# CoproMKII_Coprocessor.net
KiCad netlist of a schematic drawn in Altium Designer
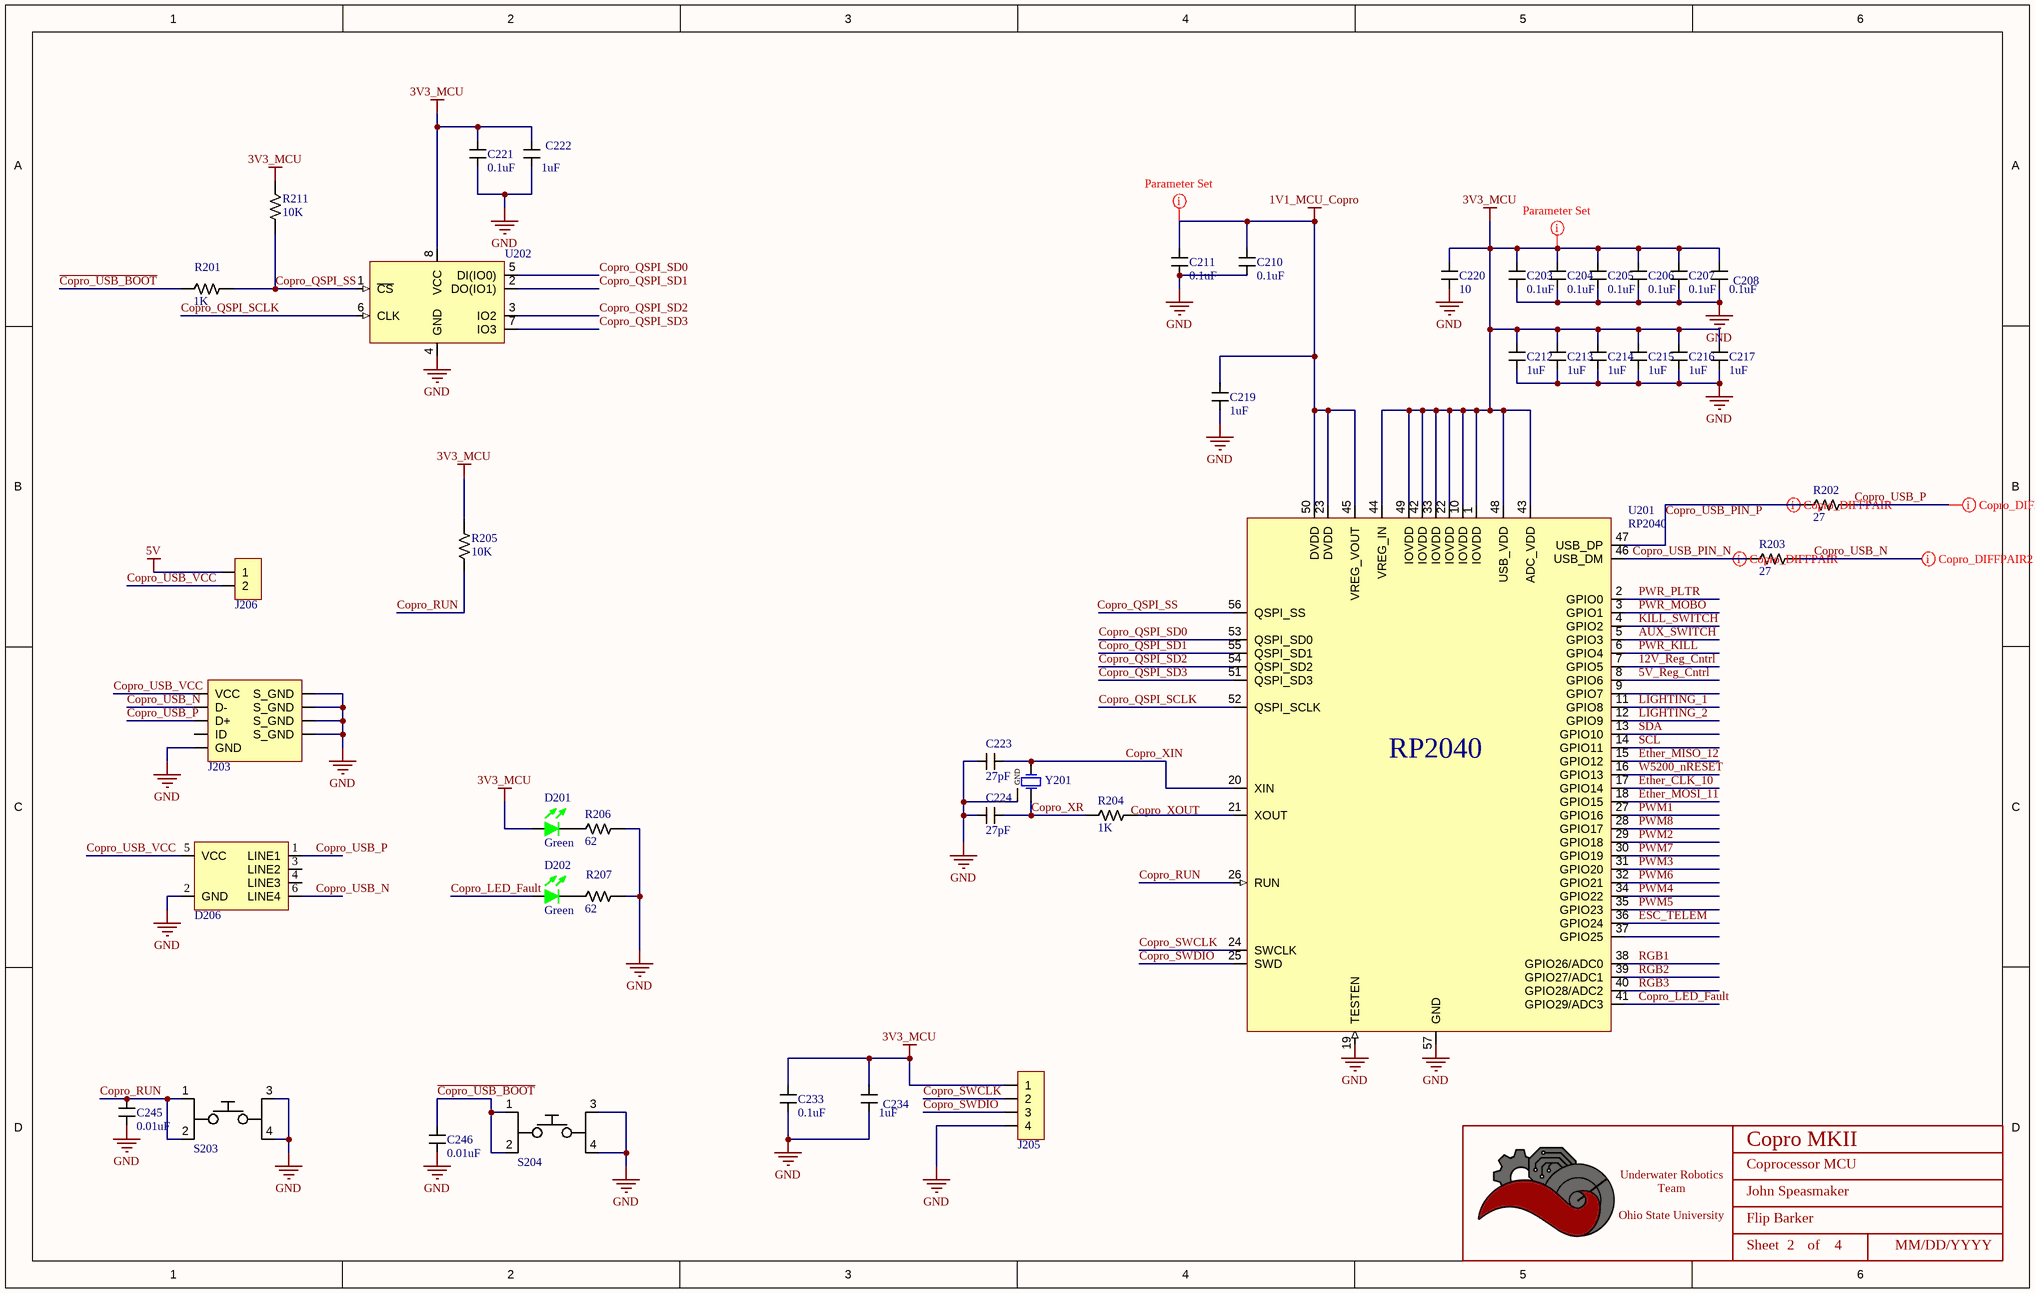
[diagram p0: CoproMKII_Coprocessor.SchDoc]

(export (version "E")
  (design (tool "Eeschema 10.0.6"))
  (components
    (comp (ref "C203")
      (value "0.1uF")
      (footprint "CAPACITOR_0603")
      (description "Cap 100nF 6.3V +/-10%\r\nCeramic 0603")
      (fields
        (field (name "TOLERANCE") "+/- 10%")
        (field (name "VOLTAGE") "6.3V")
        (field (name "MADE BY") "Flip B")
      )
      (libsource (lib "Capacitors") (part "CAPACITOR_0.1uF_0603"))
    )
    (comp (ref "C204")
      (value "0.1uF")
      (footprint "CAPACITOR_0603")
      (description "Cap 100nF 6.3V +/-10%\r\nCeramic 0603")
      (fields
        (field (name "TOLERANCE") "+/- 10%")
        (field (name "VOLTAGE") "6.3V")
        (field (name "MADE BY") "Flip B")
      )
      (libsource (lib "Capacitors") (part "CAPACITOR_0.1uF_0603"))
    )
    (comp (ref "C205")
      (value "0.1uF")
      (footprint "CAPACITOR_0603")
      (description "Cap 100nF 6.3V +/-10%\r\nCeramic 0603")
      (fields
        (field (name "TOLERANCE") "+/- 10%")
        (field (name "VOLTAGE") "6.3V")
        (field (name "MADE BY") "Flip B")
      )
      (libsource (lib "Capacitors") (part "CAPACITOR_0.1uF_0603"))
    )
    (comp (ref "C206")
      (value "0.1uF")
      (footprint "CAPACITOR_0603")
      (description "Cap 100nF 6.3V +/-10%\r\nCeramic 0603")
      (fields
        (field (name "TOLERANCE") "+/- 10%")
        (field (name "VOLTAGE") "6.3V")
        (field (name "MADE BY") "Flip B")
      )
      (libsource (lib "Capacitors") (part "CAPACITOR_0.1uF_0603"))
    )
    (comp (ref "C207")
      (value "0.1uF")
      (footprint "CAPACITOR_0603")
      (description "Cap 100nF 6.3V +/-10%\r\nCeramic 0603")
      (fields
        (field (name "TOLERANCE") "+/- 10%")
        (field (name "VOLTAGE") "6.3V")
        (field (name "MADE BY") "Flip B")
      )
      (libsource (lib "Capacitors") (part "CAPACITOR_0.1uF_0603"))
    )
    (comp (ref "C208")
      (value "0.1uF")
      (footprint "CAPACITOR_0603")
      (description "Cap 100nF 6.3V +/-10%\r\nCeramic 0603")
      (fields
        (field (name "TOLERANCE") "+/- 10%")
        (field (name "VOLTAGE") "6.3V")
        (field (name "MADE BY") "Flip B")
      )
      (libsource (lib "Capacitors") (part "CAPACITOR_0.1uF_0603"))
    )
    (comp (ref "C210")
      (value "0.1uF")
      (footprint "CAPACITOR_0603")
      (description "Cap 100nF 6.3V +/-10%\r\nCeramic 0603")
      (fields
        (field (name "TOLERANCE") "+/- 10%")
        (field (name "VOLTAGE") "6.3V")
        (field (name "MADE BY") "Flip B")
      )
      (libsource (lib "Capacitors") (part "CAPACITOR_0.1uF_0603"))
    )
    (comp (ref "C211")
      (value "0.1uF")
      (footprint "CAPACITOR_0603")
      (description "Cap 100nF 6.3V +/-10%\r\nCeramic 0603")
      (fields
        (field (name "TOLERANCE") "+/- 10%")
        (field (name "VOLTAGE") "6.3V")
        (field (name "MADE BY") "Flip B")
      )
      (libsource (lib "Capacitors") (part "CAPACITOR_0.1uF_0603"))
    )
    (comp (ref "C212")
      (value "1uF")
      (footprint "CAPACITOR_0603")
      (description "Cap 1uF 16V +/-10%\r\nCeramic 0603")
      (fields
        (field (name "TOLERANCE") "+/- 10%")
        (field (name "VOLTAGE") "16V")
        (field (name "MADE BY") "Flip B")
      )
      (libsource (lib "Capacitors") (part "CAPACITOR_1uF_0603"))
    )
    (comp (ref "C213")
      (value "1uF")
      (footprint "CAPACITOR_0603")
      (description "Cap 1uF 16V +/-10%\r\nCeramic 0603")
      (fields
        (field (name "TOLERANCE") "+/- 10%")
        (field (name "VOLTAGE") "16V")
        (field (name "MADE BY") "Flip B")
      )
      (libsource (lib "Capacitors") (part "CAPACITOR_1uF_0603"))
    )
    (comp (ref "C214")
      (value "1uF")
      (footprint "CAPACITOR_0603")
      (description "Cap 1uF 16V +/-10%\r\nCeramic 0603")
      (fields
        (field (name "TOLERANCE") "+/- 10%")
        (field (name "VOLTAGE") "16V")
        (field (name "MADE BY") "Flip B")
      )
      (libsource (lib "Capacitors") (part "CAPACITOR_1uF_0603"))
    )
    (comp (ref "C215")
      (value "1uF")
      (footprint "CAPACITOR_0603")
      (description "Cap 1uF 16V +/-10%\r\nCeramic 0603")
      (fields
        (field (name "TOLERANCE") "+/- 10%")
        (field (name "VOLTAGE") "16V")
        (field (name "MADE BY") "Flip B")
      )
      (libsource (lib "Capacitors") (part "CAPACITOR_1uF_0603"))
    )
    (comp (ref "C216")
      (value "1uF")
      (footprint "CAPACITOR_0603")
      (description "Cap 1uF 16V +/-10%\r\nCeramic 0603")
      (fields
        (field (name "TOLERANCE") "+/- 10%")
        (field (name "VOLTAGE") "16V")
        (field (name "MADE BY") "Flip B")
      )
      (libsource (lib "Capacitors") (part "CAPACITOR_1uF_0603"))
    )
    (comp (ref "C217")
      (value "1uF")
      (footprint "CAPACITOR_0603")
      (description "Cap 1uF 16V +/-10%\r\nCeramic 0603")
      (fields
        (field (name "TOLERANCE") "+/- 10%")
        (field (name "VOLTAGE") "16V")
        (field (name "MADE BY") "Flip B")
      )
      (libsource (lib "Capacitors") (part "CAPACITOR_1uF_0603"))
    )
    (comp (ref "C219")
      (value "1uF")
      (footprint "CAPACITOR_0603")
      (description "Cap 1uF 16V +/-10%\r\nCeramic 0603")
      (fields
        (field (name "TOLERANCE") "+/- 10%")
        (field (name "VOLTAGE") "16V")
        (field (name "MADE BY") "Flip B")
      )
      (libsource (lib "Capacitors") (part "CAPACITOR_1uF_0603"))
    )
    (comp (ref "C220")
      (value "10uF Ceramic 6.3V")
      (footprint "CAPACITOR_0603")
      (description "Cap 10uF 6.3V +/-20%\r\nCeramic 0603")
      (fields
        (field (name "TOLERANCE") "+/- 20%")
        (field (name "VOLTAGE") "6.3V")
        (field (name "VALUE (UF)") "10")
        (field (name "MADE BY") "Flip B")
      )
      (libsource (lib "Capacitors") (part "CAPACITOR_10uF_0603"))
    )
    (comp (ref "C221")
      (value "0.1uF")
      (footprint "CAPACITOR_0603")
      (description "Cap 100nF 6.3V +/-10%\r\nCeramic 0603")
      (fields
        (field (name "TOLERANCE") "+/- 10%")
        (field (name "VOLTAGE") "6.3V")
        (field (name "MADE BY") "Flip B")
      )
      (libsource (lib "Capacitors") (part "CAPACITOR_0.1uF_0603"))
    )
    (comp (ref "C222")
      (value "1uF")
      (footprint "CAPACITOR_0603")
      (description "Cap 1uF 16V +/-10%\r\nCeramic 0603")
      (fields
        (field (name "TOLERANCE") "+/- 10%")
        (field (name "VOLTAGE") "16V")
        (field (name "MADE BY") "Flip B")
      )
      (libsource (lib "Capacitors") (part "CAPACITOR_1uF_0603"))
    )
    (comp (ref "C223")
      (value "27pF")
      (footprint "CAPACITOR_0603")
      (description "Cap 27pF 50V +/-5%\r\nCeramic 0603")
      (fields
        (field (name "TOLERANCE") "+/- 5%")
        (field (name "VOLTAGE") "50V")
        (field (name "MADE BY") "Flip B")
      )
      (libsource (lib "Capacitors") (part "CAPACITOR_0.000027uF_0603"))
    )
    (comp (ref "C224")
      (value "27pF")
      (footprint "CAPACITOR_0603")
      (description "Cap 27pF 50V +/-5%\r\nCeramic 0603")
      (fields
        (field (name "TOLERANCE") "+/- 5%")
        (field (name "VOLTAGE") "50V")
        (field (name "MADE BY") "Flip B")
      )
      (libsource (lib "Capacitors") (part "CAPACITOR_0.000027uF_0603"))
    )
    (comp (ref "C233")
      (value "0.1uF")
      (footprint "CAPACITOR_0603")
      (description "Cap 100nF 6.3V +/-10%\r\nCeramic 0603")
      (fields
        (field (name "TOLERANCE") "+/- 10%")
        (field (name "VOLTAGE") "6.3V")
        (field (name "MADE BY") "Flip B")
      )
      (libsource (lib "Capacitors") (part "CAPACITOR_0.1uF_0603"))
    )
    (comp (ref "C234")
      (value "1uF")
      (footprint "CAPACITOR_0603")
      (description "Cap 1uF 16V +/-10%\r\nCeramic 0603")
      (fields
        (field (name "TOLERANCE") "+/- 10%")
        (field (name "VOLTAGE") "16V")
        (field (name "MADE BY") "Flip B")
      )
      (libsource (lib "Capacitors") (part "CAPACITOR_1uF_0603"))
    )
    (comp (ref "C245")
      (value "0.01uF")
      (footprint "CAPACITOR_0603")
      (description "Cap 10nF 6.3V +/-20%\r\nCeramic 0603")
      (fields
        (field (name "TOLERANCE") "+/- 10%")
        (field (name "VOLTAGE") "6.3V")
        (field (name "MADE BY") "Flip B")
      )
      (libsource (lib "Capacitors") (part "CAPACITOR_0.01uF_0603"))
    )
    (comp (ref "C246")
      (value "0.01uF")
      (footprint "CAPACITOR_0603")
      (description "Cap 10nF 6.3V +/-20%\r\nCeramic 0603")
      (fields
        (field (name "TOLERANCE") "+/- 10%")
        (field (name "VOLTAGE") "6.3V")
        (field (name "MADE BY") "Flip B")
      )
      (libsource (lib "Capacitors") (part "CAPACITOR_0.01uF_0603"))
    )
    (comp (ref "D201")
      (value "IN-S63AT5G")
      (footprint "LED_0603")
      (description "LED Green Vf= 3V If = 0.005A\r\nIN-S63AT5G")
      (fields (field (name "COLOR") "Green") (field (name "MADE BY") "Robert Pafford"))
      (libsource (lib "Diodes") (part "LED_Green_0603_3V"))
    )
    (comp (ref "D202")
      (value "IN-S63AT5G")
      (footprint "LED_0603")
      (description "LED Green Vf= 3V If = 0.005A\r\nIN-S63AT5G")
      (fields (field (name "COLOR") "Green") (field (name "MADE BY") "Robert Pafford"))
      (libsource (lib "Diodes") (part "LED_Green_0603_3V"))
    )
    (comp (ref "D206")
      (value "TVS DIODE 5VWM 25VC SOT23-6")
      (footprint "SOT 23-6L")
      (description "25V Clamp 6A (8/20µs) Ipp Tvs Diode Surface Mount SOT-23-6")
      (fields (field (name "MADE BY") "Robert Pafford"))
      (libsource (lib "Diodes") (part "RCLAMP0504S.TCT"))
    )
    (comp (ref "J203")
      (value "USB_MICRO R/A")
      (footprint "CONN_MINIUSB")
      (description "Amphenol Micro USB-B\r\nUSB2.0 5 Pin Right Angle SMD")
      (fields (field (name "MANUFACTURER") "Amphenol") (field (name "CREATED BY") "Flip B"))
      (libsource (lib "Connectors") (part "CONN_MICROUSB"))
    )
    (comp (ref "J205")
      (value "CONN HEADER VERT 4POS 2.54MM")
      (footprint "HEADER_4PIN_2.54MM")
      (fields (field (name "MADE BY") "Robert Pafford"))
      (libsource (lib "Connectors") (part "HEADER_4PIN_2.54MM"))
    )
    (comp (ref "J206")
      (value "2 POS")
      (footprint "HEADER_2PIN_2.54MM")
      (description "CONN HEADER VERT 2POS 2.54MM")
      (fields (field (name "CREATED BY") "Robert P"))
      (libsource (lib "Connectors") (part "HEADER_2PIN_2.54MM"))
    )
    (comp (ref "R201")
      (value "1k Ohm 5% 1/8W")
      (footprint "RESISTOR_0603")
      (description "RES 1k OHM 5% 1/8W 0603")
      (fields
        (field (name "TOLERANCE") "+/- 5%")
        (field (name "VALUE  (OHMS)") "1K")
        (field (name "MADE BY") "Robert Pafford")
      )
      (libsource (lib "Resistors") (part "RESISTOR_1K_0603"))
    )
    (comp (ref "R202")
      (value "27 Ohm 5% 1/8W")
      (footprint "RESISTOR_0603")
      (description "RES 27 OHM 5% 1/8W 0603")
      (fields
        (field (name "TOLERANCE") "+/- 5%")
        (field (name "VALUE  (OHMS)") "27")
        (field (name "MADE BY") "Robert Pafford")
      )
      (libsource (lib "Resistors") (part "RESISTOR_27_0603"))
    )
    (comp (ref "R203")
      (value "27 Ohm 5% 1/8W")
      (footprint "RESISTOR_0603")
      (description "RES 27 OHM 5% 1/8W 0603")
      (fields
        (field (name "TOLERANCE") "+/- 5%")
        (field (name "VALUE  (OHMS)") "27")
        (field (name "MADE BY") "Robert Pafford")
      )
      (libsource (lib "Resistors") (part "RESISTOR_27_0603"))
    )
    (comp (ref "R204")
      (value "1k Ohm 5% 1/8W")
      (footprint "RESISTOR_0603")
      (description "RES 1k OHM 5% 1/8W 0603")
      (fields
        (field (name "TOLERANCE") "+/- 5%")
        (field (name "VALUE  (OHMS)") "1K")
        (field (name "MADE BY") "Robert Pafford")
      )
      (libsource (lib "Resistors") (part "RESISTOR_1K_0603"))
    )
    (comp (ref "R205")
      (value "10k Ohm 5% 1/10W")
      (footprint "RESISTOR_0603")
      (description "RES 10k OHM 5% 1/10W 0603")
      (fields
        (field (name "TOLERANCE") "+/- 5%")
        (field (name "VALUE  (OHMS)") "10K")
        (field (name "MADE BY") "Robert Pafford")
      )
      (libsource (lib "Resistors") (part "RESISTOR_10K_0603"))
    )
    (comp (ref "R206")
      (value "62 Ohm 1% 1/4W")
      (footprint "RESISTOR_0603")
      (description "RES SMD 62 OHM 1% 1/4W 0603")
      (fields
        (field (name "TOLERANCE") "+/- 1%")
        (field (name "VALUE  (OHMS)") "62")
        (field (name "MADE BY") "Robert Pafford")
      )
      (libsource (lib "Resistors") (part "RESISTOR_62_0603"))
    )
    (comp (ref "R207")
      (value "62 Ohm 1% 1/4W")
      (footprint "RESISTOR_0603")
      (description "RES SMD 62 OHM 1% 1/4W 0603")
      (fields
        (field (name "TOLERANCE") "+/- 1%")
        (field (name "VALUE  (OHMS)") "62")
        (field (name "MADE BY") "Robert Pafford")
      )
      (libsource (lib "Resistors") (part "RESISTOR_62_0603"))
    )
    (comp (ref "R211")
      (value "10k Ohm 5% 1/10W")
      (footprint "RESISTOR_0603")
      (description "RES 10k OHM 5% 1/10W 0603")
      (fields
        (field (name "TOLERANCE") "+/- 5%")
        (field (name "VALUE  (OHMS)") "10K")
        (field (name "MADE BY") "Robert Pafford")
      )
      (libsource (lib "Resistors") (part "RESISTOR_10K_0603"))
    )
    (comp (ref "S203")
      (value "SPST Tactile Switch")
      (footprint "TactileSwitch")
      (description "SWITCH TACTILE SPST-NO 0.05A 12V")
      (fields (field (name "MADE BY") "Robert Pafford"))
      (libsource (lib "Switches") (part "Tactile Switch"))
    )
    (comp (ref "S204")
      (value "SPST Tactile Switch")
      (footprint "TactileSwitch")
      (description "SWITCH TACTILE SPST-NO 0.05A 12V")
      (fields (field (name "MADE BY") "Robert Pafford"))
      (libsource (lib "Switches") (part "Tactile Switch"))
    )
    (comp (ref "U201")
      (value "RP2040")
      (footprint "QFN-56 RP2040")
      (description "Raspberry Pi RP2040")
      (fields (field (name "MADE BY") "Robert Pafford"))
      (libsource (lib "Integrated Circuits") (part "RP2040"))
    )
    (comp (ref "U202")
      (value "W25Q128JVSIQ")
      (footprint "SOIC-8 W25QxJV")
      (description "IC FLASH 128MBIT SPI/QUAD 8SOIC")
      (fields (field (name "MADE BY") "Robert Pafford"))
      (libsource (lib "Integrated Circuits") (part "W25Q128JVSIQ"))
    )
    (comp (ref "Y201")
      (value "CRYSTAL 12.0000MHZ 18PF SMD")
      (footprint "4-SMD No Lead Crystal")
      (description "12 MHz ±20ppm Crystal 18pF 50 Ohms 4-SMD, No Lead")
      (fields (field (name "MADE BY") "Siddharth Venkatesan"))
      (libsource (lib "Crystals") (part "CRYSTAL_12MHz_SMD"))
    )
  )
  (nets
    (net (code "1") (name "/5V_Reg_Cntrl") (class "Default")
      (node (ref "U201") (pin "8") (pinfunction "GPIO6_8") (pintype "bidirectional"))
    )
    (net (code "2") (name "/12V_Reg_Cntrl") (class "Default")
      (node (ref "U201") (pin "7") (pinfunction "GPIO5_7") (pintype "bidirectional"))
    )
    (net (code "3") (name "/AUX_SWITCH") (class "Default")
      (node (ref "U201") (pin "5") (pinfunction "GPIO3_5") (pintype "bidirectional"))
    )
    (net (code "4") (name "/Copro_LED_Fault") (class "Default")
      (node (ref "D202") (pin "1") (pinfunction "1_1") (pintype "passive"))
      (node (ref "U201") (pin "41") (pinfunction "GPIO29/ADC3_41") (pintype "bidirectional"))
    )
    (net (code "5") (name "/Copro_QSPI_SCLK") (class "Default")
      (node (ref "U201") (pin "52") (pinfunction "QSPI_SCLK_52") (pintype "bidirectional"))
      (node (ref "U202") (pin "6") (pinfunction "CLK_6") (pintype "input"))
    )
    (net (code "6") (name "/Copro_QSPI_SD0") (class "Default")
      (node (ref "U201") (pin "53") (pinfunction "QSPI_SD0_53") (pintype "bidirectional"))
      (node (ref "U202") (pin "5") (pinfunction "DI(IO0)_5") (pintype "bidirectional"))
    )
    (net (code "7") (name "/Copro_QSPI_SD1") (class "Default")
      (node (ref "U201") (pin "55") (pinfunction "QSPI_SD1_55") (pintype "bidirectional"))
      (node (ref "U202") (pin "2") (pinfunction "DO(IO1)_2") (pintype "bidirectional"))
    )
    (net (code "8") (name "/Copro_QSPI_SD2") (class "Default")
      (node (ref "U201") (pin "54") (pinfunction "QSPI_SD2_54") (pintype "bidirectional"))
      (node (ref "U202") (pin "3") (pinfunction "IO2_3") (pintype "bidirectional"))
    )
    (net (code "9") (name "/Copro_QSPI_SD3") (class "Default")
      (node (ref "U201") (pin "51") (pinfunction "QSPI_SD3_51") (pintype "bidirectional"))
      (node (ref "U202") (pin "7") (pinfunction "IO3_7") (pintype "bidirectional"))
    )
    (net (code "10") (name "/Copro_QSPI_SS") (class "Default")
      (node (ref "R201") (pin "1") (pinfunction "1_1") (pintype "passive"))
      (node (ref "R211") (pin "1") (pinfunction "1_1") (pintype "passive"))
      (node (ref "U201") (pin "56") (pinfunction "QSPI_SS_56") (pintype "bidirectional"))
      (node (ref "U202") (pin "1") (pinfunction "~{CS}_1") (pintype "input"))
    )
    (net (code "11") (name "/Copro_RUN") (class "Default")
      (node (ref "C245") (pin "1") (pinfunction "1_1") (pintype "passive"))
      (node (ref "R205") (pin "2") (pinfunction "2_2") (pintype "passive"))
      (node (ref "S203") (pin "1") (pinfunction "1_1") (pintype "passive"))
      (node (ref "S203") (pin "2") (pinfunction "2_2") (pintype "passive"))
      (node (ref "U201") (pin "26") (pinfunction "RUN_26") (pintype "input"))
    )
    (net (code "12") (name "/Copro_SWCLK") (class "Default")
      (node (ref "J205") (pin "2") (pinfunction "2_2") (pintype "passive"))
      (node (ref "U201") (pin "24") (pinfunction "SWCLK_24") (pintype "bidirectional"))
    )
    (net (code "13") (name "/Copro_SWDIO") (class "Default")
      (node (ref "J205") (pin "3") (pinfunction "3_3") (pintype "passive"))
      (node (ref "U201") (pin "25") (pinfunction "SWD_25") (pintype "bidirectional"))
    )
    (net (code "14") (name "/Copro_USB_N") (class "Default")
      (node (ref "D206") (pin "6") (pinfunction "LINE4_6") (pintype "passive"))
      (node (ref "J203") (pin "2") (pinfunction "D-_2") (pintype "passive"))
      (node (ref "R203") (pin "1") (pinfunction "1_1") (pintype "passive"))
    )
    (net (code "15") (name "/Copro_USB_P") (class "Default")
      (node (ref "D206") (pin "1") (pinfunction "LINE1_1") (pintype "passive"))
      (node (ref "J203") (pin "3") (pinfunction "D+_3") (pintype "passive"))
      (node (ref "R202") (pin "1") (pinfunction "1_1") (pintype "passive"))
    )
    (net (code "16") (name "/Copro_USB_PIN_N") (class "Default")
      (node (ref "R203") (pin "2") (pinfunction "2_2") (pintype "passive"))
      (node (ref "U201") (pin "46") (pinfunction "USB_DM_46") (pintype "bidirectional"))
    )
    (net (code "17") (name "/Copro_USB_PIN_P") (class "Default")
      (node (ref "R202") (pin "2") (pinfunction "2_2") (pintype "passive"))
      (node (ref "U201") (pin "47") (pinfunction "USB_DP_47") (pintype "bidirectional"))
    )
    (net (code "18") (name "/Copro_USB_VCC") (class "Default")
      (node (ref "D206") (pin "5") (pinfunction "VCC_5") (pintype "power_in"))
      (node (ref "J203") (pin "1") (pinfunction "VCC_1") (pintype "passive"))
      (node (ref "J206") (pin "2") (pinfunction "2_2") (pintype "passive"))
    )
    (net (code "19") (name "/Copro_XIN") (class "Default")
      (node (ref "C223") (pin "1") (pinfunction "1_1") (pintype "passive"))
      (node (ref "U201") (pin "20") (pinfunction "XIN_20") (pintype "passive"))
      (node (ref "Y201") (pin "1") (pinfunction "1_1") (pintype "passive"))
    )
    (net (code "21") (name "/Copro_XR") (class "Default")
      (node (ref "C224") (pin "1") (pinfunction "1_1") (pintype "passive"))
      (node (ref "R204") (pin "2") (pinfunction "2_2") (pintype "passive"))
      (node (ref "Y201") (pin "2") (pinfunction "2_2") (pintype "passive"))
    )
    (net (code "22") (name "/ESC_TELEM") (class "Default")
      (node (ref "U201") (pin "36") (pinfunction "GPIO24_36") (pintype "bidirectional"))
    )
    (net (code "23") (name "/Ether_CLK_10") (class "Default")
      (node (ref "U201") (pin "17") (pinfunction "GPIO14_17") (pintype "bidirectional"))
    )
    (net (code "24") (name "/Ether_MISO_12") (class "Default")
      (node (ref "U201") (pin "15") (pinfunction "GPIO12_15") (pintype "bidirectional"))
    )
    (net (code "25") (name "/Ether_MOSI_11") (class "Default")
      (node (ref "U201") (pin "18") (pinfunction "GPIO15_18") (pintype "bidirectional"))
    )
    (net (code "26") (name "/KILL_SWITCH") (class "Default")
      (node (ref "U201") (pin "4") (pinfunction "GPIO2_4") (pintype "bidirectional"))
    )
    (net (code "27") (name "/LIGHTING_1") (class "Default")
      (node (ref "U201") (pin "11") (pinfunction "GPIO8_11") (pintype "bidirectional"))
    )
    (net (code "28") (name "/LIGHTING_2") (class "Default")
      (node (ref "U201") (pin "12") (pinfunction "GPIO9_12") (pintype "bidirectional"))
    )
    (net (code "29") (name "/PWM1") (class "Default")
      (node (ref "U201") (pin "27") (pinfunction "GPIO16_27") (pintype "bidirectional"))
    )
    (net (code "30") (name "/PWM2") (class "Default")
      (node (ref "U201") (pin "29") (pinfunction "GPIO18_29") (pintype "bidirectional"))
    )
    (net (code "31") (name "/PWM3") (class "Default")
      (node (ref "U201") (pin "31") (pinfunction "GPIO20_31") (pintype "bidirectional"))
    )
    (net (code "32") (name "/PWM4") (class "Default")
      (node (ref "U201") (pin "34") (pinfunction "GPIO22_34") (pintype "bidirectional"))
    )
    (net (code "33") (name "/PWM5") (class "Default")
      (node (ref "U201") (pin "35") (pinfunction "GPIO23_35") (pintype "bidirectional"))
    )
    (net (code "34") (name "/PWM6") (class "Default")
      (node (ref "U201") (pin "32") (pinfunction "GPIO21_32") (pintype "bidirectional"))
    )
    (net (code "35") (name "/PWM7") (class "Default")
      (node (ref "U201") (pin "30") (pinfunction "GPIO19_30") (pintype "bidirectional"))
    )
    (net (code "36") (name "/PWM8") (class "Default")
      (node (ref "U201") (pin "28") (pinfunction "GPIO17_28") (pintype "bidirectional"))
    )
    (net (code "37") (name "/PWR_KILL") (class "Default")
      (node (ref "U201") (pin "6") (pinfunction "GPIO4_6") (pintype "bidirectional"))
    )
    (net (code "38") (name "/PWR_MOBO") (class "Default")
      (node (ref "U201") (pin "3") (pinfunction "GPIO1_3") (pintype "bidirectional"))
    )
    (net (code "39") (name "/PWR_PLTR") (class "Default")
      (node (ref "U201") (pin "2") (pinfunction "GPIO0_2") (pintype "bidirectional"))
    )
    (net (code "40") (name "/RGB1") (class "Default")
      (node (ref "U201") (pin "38") (pinfunction "GPIO26/ADC0_38") (pintype "bidirectional"))
    )
    (net (code "41") (name "/RGB2") (class "Default")
      (node (ref "U201") (pin "39") (pinfunction "GPIO27/ADC1_39") (pintype "bidirectional"))
    )
    (net (code "42") (name "/RGB3") (class "Default")
      (node (ref "U201") (pin "40") (pinfunction "GPIO28/ADC2_40") (pintype "bidirectional"))
    )
    (net (code "43") (name "/SCL") (class "Default")
      (node (ref "U201") (pin "14") (pinfunction "GPIO11_14") (pintype "bidirectional"))
    )
    (net (code "44") (name "/SDA") (class "Default")
      (node (ref "U201") (pin "13") (pinfunction "GPIO10_13") (pintype "bidirectional"))
    )
    (net (code "45") (name "/W5200_nRESET") (class "Default")
      (node (ref "U201") (pin "16") (pinfunction "GPIO13_16") (pintype "bidirectional"))
    )
    (net (code "46") (name "/~{Copro_USB_BOOT}") (class "Default")
      (node (ref "C246") (pin "1") (pinfunction "1_1") (pintype "passive"))
      (node (ref "R201") (pin "2") (pinfunction "2_2") (pintype "passive"))
      (node (ref "S204") (pin "1") (pinfunction "1_1") (pintype "passive"))
      (node (ref "S204") (pin "2") (pinfunction "2_2") (pintype "passive"))
    )
    (net (code "47") (name "1V1_MCU_Copro") (class "Default")
      (node (ref "C210") (pin "2") (pinfunction "2_2") (pintype "passive"))
      (node (ref "C211") (pin "2") (pinfunction "2_2") (pintype "passive"))
      (node (ref "C219") (pin "2") (pinfunction "2_2") (pintype "passive"))
      (node (ref "U201") (pin "23") (pinfunction "DVDD_23") (pintype "power_in"))
      (node (ref "U201") (pin "45") (pinfunction "VREG_VOUT_45") (pintype "power_in"))
      (node (ref "U201") (pin "50") (pinfunction "DVDD_50") (pintype "power_in"))
    )
    (net (code "48") (name "3V3_MCU") (class "Default")
      (node (ref "C203") (pin "2") (pinfunction "2_2") (pintype "passive"))
      (node (ref "C204") (pin "2") (pinfunction "2_2") (pintype "passive"))
      (node (ref "C205") (pin "2") (pinfunction "2_2") (pintype "passive"))
      (node (ref "C206") (pin "2") (pinfunction "2_2") (pintype "passive"))
      (node (ref "C207") (pin "2") (pinfunction "2_2") (pintype "passive"))
      (node (ref "C208") (pin "2") (pinfunction "2_2") (pintype "passive"))
      (node (ref "C212") (pin "2") (pinfunction "2_2") (pintype "passive"))
      (node (ref "C213") (pin "2") (pinfunction "2_2") (pintype "passive"))
      (node (ref "C214") (pin "2") (pinfunction "2_2") (pintype "passive"))
      (node (ref "C215") (pin "2") (pinfunction "2_2") (pintype "passive"))
      (node (ref "C216") (pin "2") (pinfunction "2_2") (pintype "passive"))
      (node (ref "C217") (pin "2") (pinfunction "2_2") (pintype "passive"))
      (node (ref "C220") (pin "2") (pinfunction "2_2") (pintype "passive"))
      (node (ref "C221") (pin "1") (pinfunction "1_1") (pintype "passive"))
      (node (ref "C222") (pin "1") (pinfunction "1_1") (pintype "passive"))
      (node (ref "C233") (pin "1") (pinfunction "1_1") (pintype "passive"))
      (node (ref "C234") (pin "1") (pinfunction "1_1") (pintype "passive"))
      (node (ref "D201") (pin "1") (pinfunction "1_1") (pintype "passive"))
      (node (ref "J205") (pin "1") (pinfunction "1_1") (pintype "passive"))
      (node (ref "R205") (pin "1") (pinfunction "1_1") (pintype "passive"))
      (node (ref "R211") (pin "2") (pinfunction "2_2") (pintype "passive"))
      (node (ref "U201") (pin "1") (pinfunction "IOVDD_1") (pintype "power_in"))
      (node (ref "U201") (pin "10") (pinfunction "IOVDD_10") (pintype "power_in"))
      (node (ref "U201") (pin "22") (pinfunction "IOVDD_22") (pintype "power_in"))
      (node (ref "U201") (pin "33") (pinfunction "IOVDD_33") (pintype "power_in"))
      (node (ref "U201") (pin "42") (pinfunction "IOVDD_42") (pintype "power_in"))
      (node (ref "U201") (pin "43") (pinfunction "ADC_VDD_43") (pintype "power_in"))
      (node (ref "U201") (pin "44") (pinfunction "VREG_IN_44") (pintype "power_in"))
      (node (ref "U201") (pin "48") (pinfunction "USB_VDD_48") (pintype "power_in"))
      (node (ref "U201") (pin "49") (pinfunction "IOVDD_49") (pintype "power_in"))
      (node (ref "U202") (pin "8") (pinfunction "VCC_8") (pintype "power_in"))
    )
    (net (code "49") (name "5V") (class "Default")
      (node (ref "J206") (pin "1") (pinfunction "1_1") (pintype "passive"))
    )
    (net (code "50") (name "GND") (class "Default")
      (node (ref "C203") (pin "1") (pinfunction "1_1") (pintype "passive"))
      (node (ref "C204") (pin "1") (pinfunction "1_1") (pintype "passive"))
      (node (ref "C205") (pin "1") (pinfunction "1_1") (pintype "passive"))
      (node (ref "C206") (pin "1") (pinfunction "1_1") (pintype "passive"))
      (node (ref "C207") (pin "1") (pinfunction "1_1") (pintype "passive"))
      (node (ref "C208") (pin "1") (pinfunction "1_1") (pintype "passive"))
      (node (ref "C210") (pin "1") (pinfunction "1_1") (pintype "passive"))
      (node (ref "C211") (pin "1") (pinfunction "1_1") (pintype "passive"))
      (node (ref "C212") (pin "1") (pinfunction "1_1") (pintype "passive"))
      (node (ref "C213") (pin "1") (pinfunction "1_1") (pintype "passive"))
      (node (ref "C214") (pin "1") (pinfunction "1_1") (pintype "passive"))
      (node (ref "C215") (pin "1") (pinfunction "1_1") (pintype "passive"))
      (node (ref "C216") (pin "1") (pinfunction "1_1") (pintype "passive"))
      (node (ref "C217") (pin "1") (pinfunction "1_1") (pintype "passive"))
      (node (ref "C219") (pin "1") (pinfunction "1_1") (pintype "passive"))
      (node (ref "C220") (pin "1") (pinfunction "1_1") (pintype "passive"))
      (node (ref "C221") (pin "2") (pinfunction "2_2") (pintype "passive"))
      (node (ref "C222") (pin "2") (pinfunction "2_2") (pintype "passive"))
      (node (ref "C223") (pin "2") (pinfunction "2_2") (pintype "passive"))
      (node (ref "C224") (pin "2") (pinfunction "2_2") (pintype "passive"))
      (node (ref "C233") (pin "2") (pinfunction "2_2") (pintype "passive"))
      (node (ref "C234") (pin "2") (pinfunction "2_2") (pintype "passive"))
      (node (ref "C245") (pin "2") (pinfunction "2_2") (pintype "passive"))
      (node (ref "C246") (pin "2") (pinfunction "2_2") (pintype "passive"))
      (node (ref "D206") (pin "2") (pinfunction "GND_2") (pintype "power_in"))
      (node (ref "J203") (pin "5") (pinfunction "GND_5") (pintype "passive"))
      (node (ref "J203") (pin "6") (pinfunction "S_GND_6") (pintype "passive"))
      (node (ref "J203") (pin "7") (pinfunction "S_GND_7") (pintype "passive"))
      (node (ref "J203") (pin "8") (pinfunction "S_GND_8") (pintype "passive"))
      (node (ref "J203") (pin "9") (pinfunction "S_GND_9") (pintype "passive"))
      (node (ref "J205") (pin "4") (pinfunction "4_4") (pintype "passive"))
      (node (ref "R206") (pin "1") (pinfunction "1_1") (pintype "passive"))
      (node (ref "R207") (pin "1") (pinfunction "1_1") (pintype "passive"))
      (node (ref "S203") (pin "3") (pinfunction "3_3") (pintype "passive"))
      (node (ref "S203") (pin "4") (pinfunction "4_4") (pintype "passive"))
      (node (ref "S204") (pin "3") (pinfunction "3_3") (pintype "passive"))
      (node (ref "S204") (pin "4") (pinfunction "4_4") (pintype "passive"))
      (node (ref "U201") (pin "19") (pinfunction "TESTEN_19") (pintype "input"))
      (node (ref "U201") (pin "57") (pinfunction "GND_57") (pintype "power_in"))
      (node (ref "U202") (pin "4") (pinfunction "GND_4") (pintype "power_in"))
      (node (ref "Y201") (pin "GND") (pinfunction "GND_GND") (pintype "power_in"))
    )
    (net (code "51") (name "Net-(D201-Pad2)") (class "Default")
      (node (ref "D201") (pin "2") (pinfunction "2_2") (pintype "passive"))
      (node (ref "R206") (pin "2") (pinfunction "2_2") (pintype "passive"))
    )
    (net (code "52") (name "Net-(D202-Pad2)") (class "Default")
      (node (ref "D202") (pin "2") (pinfunction "2_2") (pintype "passive"))
      (node (ref "R207") (pin "2") (pinfunction "2_2") (pintype "passive"))
    )
    (net (code "53") (name "Net-(U201-XOUT)") (class "Default")
      (node (ref "R204") (pin "1") (pinfunction "1_1") (pintype "passive"))
      (node (ref "U201") (pin "21") (pinfunction "XOUT_21") (pintype "passive"))
    )
    (net (code "54") (name "unconnected-(D206-LINE2-Pad3)") (class "Default")
      (node (ref "D206") (pin "3") (pinfunction "LINE2_3") (pintype "passive"))
    )
    (net (code "55") (name "unconnected-(D206-LINE3-Pad4)") (class "Default")
      (node (ref "D206") (pin "4") (pinfunction "LINE3_4") (pintype "passive"))
    )
    (net (code "56") (name "unconnected-(J203-ID-Pad4)") (class "Default")
      (node (ref "J203") (pin "4") (pinfunction "ID_4") (pintype "passive"))
    )
    (net (code "57") (name "unconnected-(U201-GPIO7-Pad9)") (class "Default")
      (node (ref "U201") (pin "9") (pinfunction "GPIO7_9") (pintype "bidirectional"))
    )
    (net (code "58") (name "unconnected-(U201-GPIO25-Pad37)") (class "Default")
      (node (ref "U201") (pin "37") (pinfunction "GPIO25_37") (pintype "bidirectional"))
    )
  )
)
